# led_stairs_psu.net
KiCad netlist of a schematic drawn in EAGLE
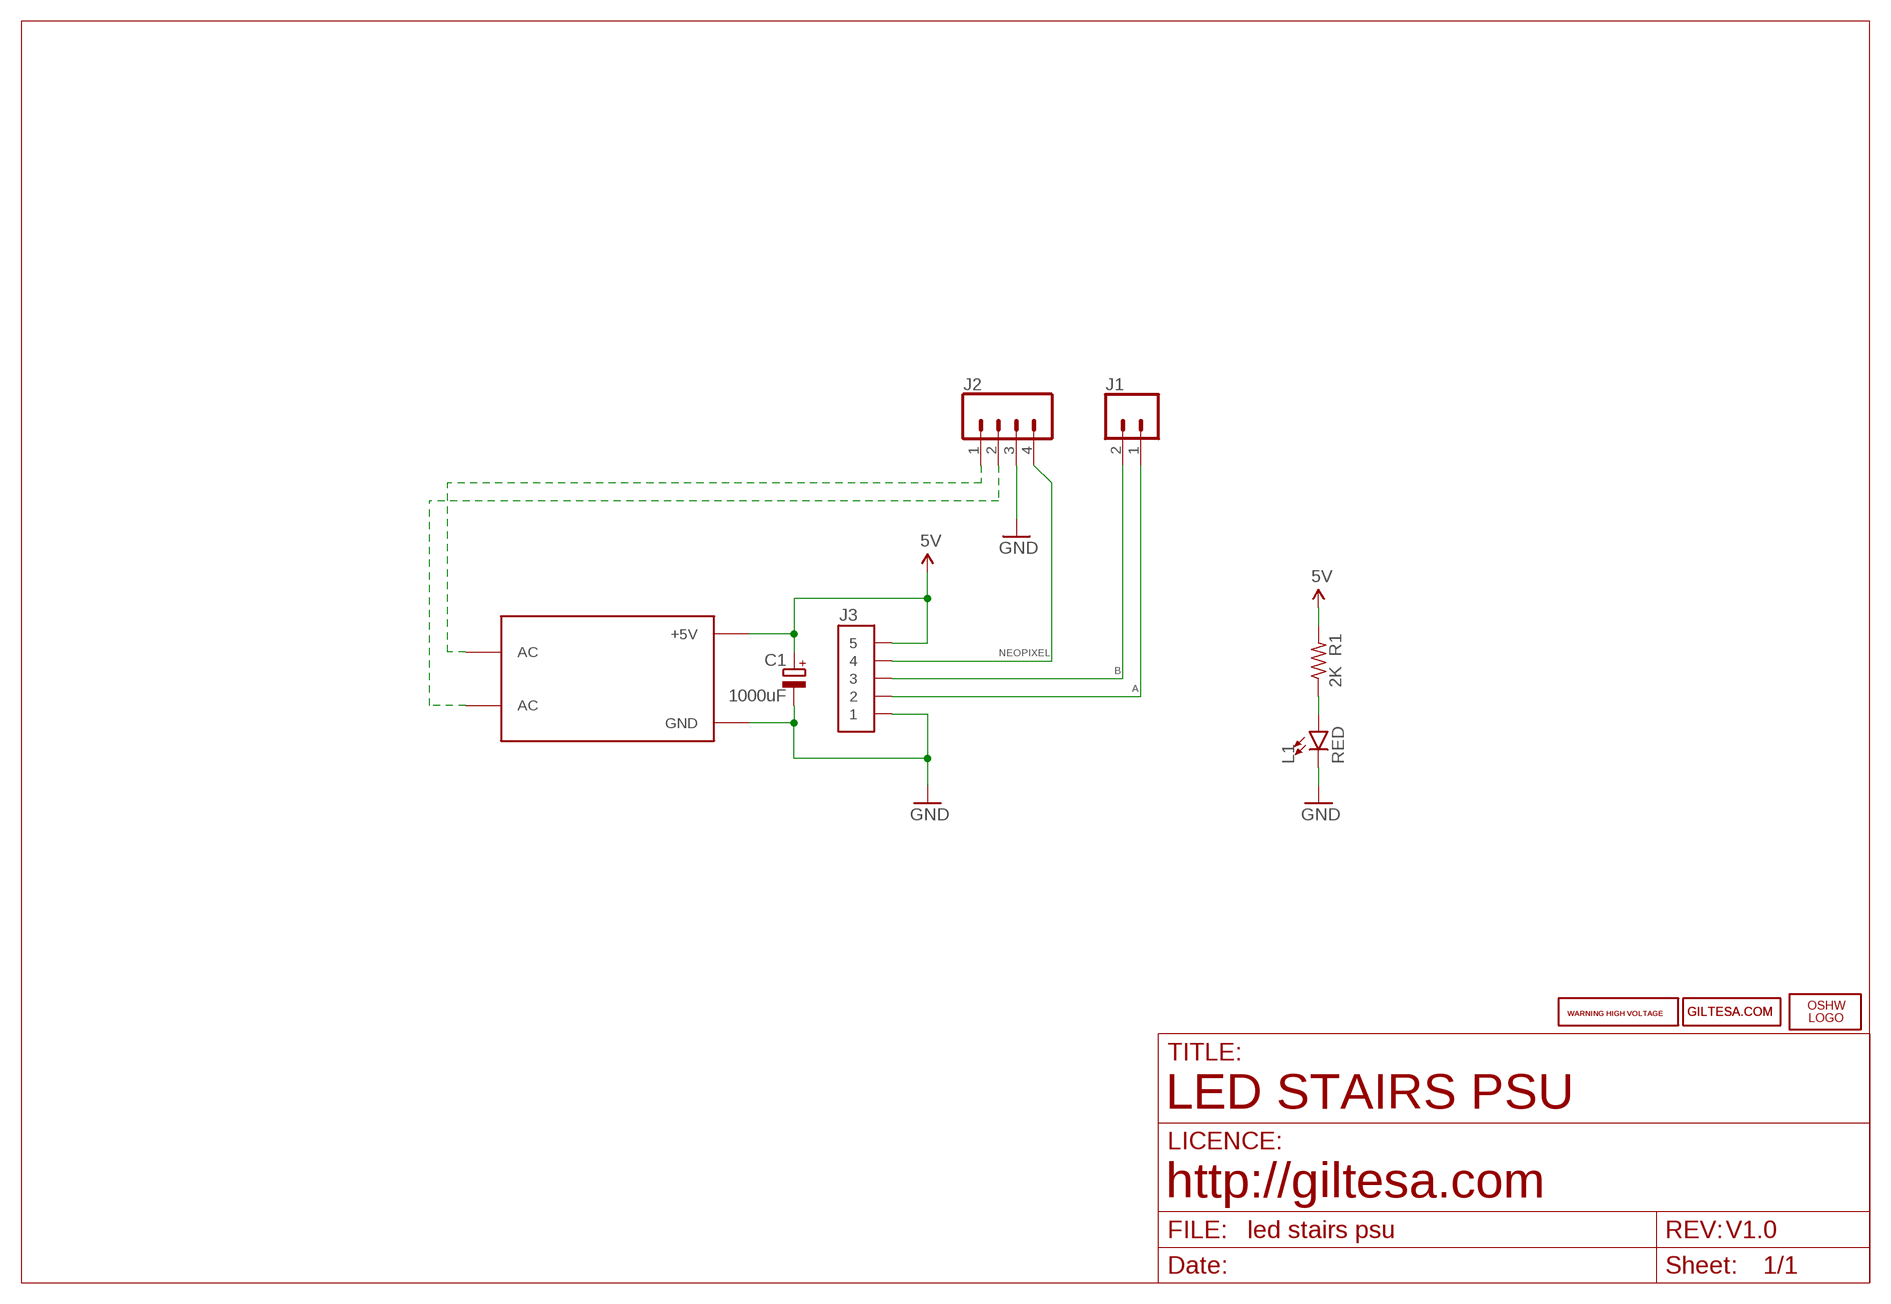
[diagram p0: schematic, sheet 1]

(export (version "E")
  (design (tool "Eeschema 10.0.6"))
  (components
    (comp (ref "C1")
      (value "1000uF")
      (footprint "eagle-import:B45181A")
      (libsource (lib "eagle-import") (part "CPOL-EUB45181A"))
    )
    (comp (ref "J1")
      (value "TERMINAL_5MM_2P1")
      (footprint "eagle-import:TERMINAL_5MM_2P")
      (libsource (lib "eagle-import") (part "TERMINAL_5MM_2P1"))
    )
    (comp (ref "J2")
      (value "TERMINAL_5MM_4P_90º_20A")
      (footprint "eagle-import:TERMINAL_5MM_4P_90º_20A")
      (libsource (lib "eagle-import") (part "TERMINAL_5MM_4P_90º_20A"))
    )
    (comp (ref "J3")
      (value "1X05")
      (footprint "eagle-import:1X5_SMT_2MM")
      (libsource (lib "eagle-import") (part "1X05"))
    )
    (comp (ref "L1")
      (value "RED")
      (footprint "eagle-import:LED-0603")
      (libsource (lib "eagle-import") (part "LED-BLUE0603"))
    )
    (comp (ref "LOGO1")
      (value "OSHW_LOGO_FILLX0150-NT")
      (footprint "eagle-import:OSHW_FILLX150_NOTEXT")
      (libsource (lib "eagle-import") (part "OSHW_LOGO_FILLX0150-NT"))
    )
    (comp (ref "R1")
      (value "2K")
      (footprint "eagle-import:R0603")
      (libsource (lib "eagle-import") (part "R0603"))
    )
    (comp (ref "U$3")
      (value "WARNING_HIGH_VOLTAGE1")
      (footprint "eagle-import:WARNING_HIGH_VOLTAGE")
      (libsource (lib "eagle-import") (part "WARNING_HIGH_VOLTAGE1"))
    )
    (comp (ref "U$6")
      (value "WARNING_HIGH_VOLTAGE1")
      (footprint "eagle-import:WARNING_HIGH_VOLTAGE")
      (libsource (lib "eagle-import") (part "WARNING_HIGH_VOLTAGE1"))
    )
    (comp (ref "U$10")
      (value "GILTESA.COM_COPPER")
      (footprint "eagle-import:GILTESA.COM_COPPER")
      (libsource (lib "eagle-import") (part "GILTESA.COM_COPPER"))
    )
    (comp (ref "U$13")
      (value "GILTESA.COM_MASK")
      (footprint "eagle-import:GILTESA.COM_MASK")
      (libsource (lib "eagle-import") (part "GILTESA.COM_MASK"))
    )
    (comp (ref "U1")
      (value "HILINK HLK-PM01 5V")
      (footprint "eagle-import:HILINK_HLK-PM01_5V")
      (libsource (lib "eagle-import") (part "HILINK_HLK-PM01_5V"))
    )
  )
  (nets
    (net (code "1") (name "/A") (class "Default")
      (node (ref "J1") (pin "1") (pinfunction "1_1") (pintype "passive"))
      (node (ref "J3") (pin "2") (pinfunction "2_2") (pintype "passive"))
    )
    (net (code "2") (name "/B") (class "Default")
      (node (ref "J1") (pin "2") (pinfunction "2_2") (pintype "passive"))
      (node (ref "J3") (pin "3") (pinfunction "3_3") (pintype "passive"))
    )
    (net (code "3") (name "/NEOPIXEL") (class "Default")
      (node (ref "J2") (pin "4") (pinfunction "4_4") (pintype "passive"))
      (node (ref "J3") (pin "4") (pinfunction "4_4") (pintype "passive"))
    )
    (net (code "4") (name "5V") (class "Default")
      (node (ref "C1") (pin "+") (pinfunction "+_+") (pintype "passive"))
      (node (ref "J3") (pin "5") (pinfunction "5_5") (pintype "passive"))
      (node (ref "R1") (pin "2") (pinfunction "2_2") (pintype "passive"))
      (node (ref "U1") (pin "+5V") (pinfunction "+5V_+5V") (pintype "output"))
    )
    (net (code "5") (name "GND") (class "Default")
      (node (ref "C1") (pin "-") (pinfunction "-_-") (pintype "passive"))
      (node (ref "J2") (pin "3") (pinfunction "3_3") (pintype "passive"))
      (node (ref "J3") (pin "1") (pinfunction "1_1") (pintype "passive"))
      (node (ref "L1") (pin "C") (pinfunction "C_C") (pintype "passive"))
      (node (ref "U1") (pin "GND") (pinfunction "GND_GND") (pintype "output"))
    )
    (net (code "6") (name "Net-(J2-Pad1)") (class "Default")
      (node (ref "J2") (pin "1") (pinfunction "1_1") (pintype "passive"))
      (node (ref "U1") (pin "AC@2") (pinfunction "AC_AC@2") (pintype "input"))
    )
    (net (code "7") (name "Net-(J2-Pad2)") (class "Default")
      (node (ref "J2") (pin "2") (pinfunction "2_2") (pintype "passive"))
      (node (ref "U1") (pin "AC@1") (pinfunction "AC_AC@1") (pintype "input"))
    )
    (net (code "8") (name "Net-(L1-PadA)") (class "Default")
      (node (ref "L1") (pin "A") (pinfunction "A_A") (pintype "passive"))
      (node (ref "R1") (pin "1") (pinfunction "1_1") (pintype "passive"))
    )
  )
)
